# buck_schematic.net
KiCad netlist of a schematic drawn in EAGLE
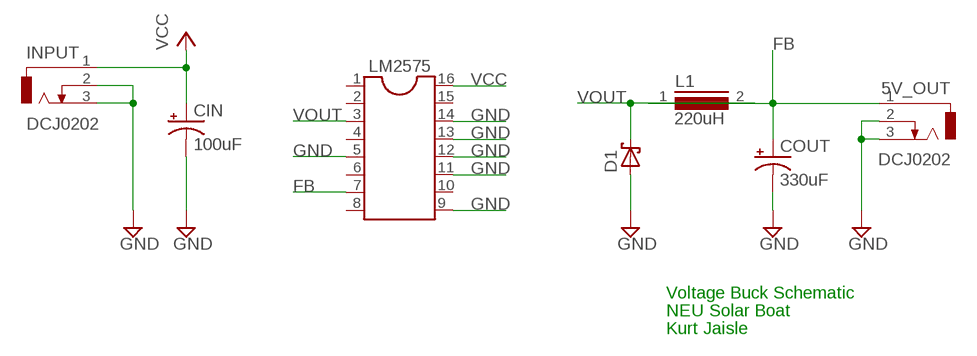
[diagram p0: schematic, sheet 1]

(export (version "E")
  (design (tool "Eeschema 10.0.6"))
  (components
    (comp (ref "5V_OUT")
      (value "DCJ0202")
      (footprint "eagle-import:DCJ0202")
      (libsource (lib "eagle-import") (part "DCJ0202"))
    )
    (comp (ref "CIN")
      (value "100uF")
      (footprint "eagle-import:E5-10,5")
      (libsource (lib "eagle-import") (part "CPOL-USE5-10.5"))
    )
    (comp (ref "COUT")
      (value "330uF")
      (footprint "eagle-import:E5-10,5")
      (libsource (lib "eagle-import") (part "CPOL-USE5-10.5"))
    )
    (comp (ref "D1")
      (value "SCHOTTKY-DIODEF126Z12")
      (footprint "eagle-import:F126Z12")
      (libsource (lib "eagle-import") (part "SCHOTTKY-DIODEF126Z12"))
    )
    (comp (ref "INPUT")
      (value "DCJ0202")
      (footprint "eagle-import:DCJ0202")
      (libsource (lib "eagle-import") (part "DCJ0202"))
    )
    (comp (ref "L1")
      (value "220uH")
      (footprint "eagle-import:SUKW3-27")
      (libsource (lib "eagle-import") (part "B82133"))
    )
    (comp (ref "LM2575")
      (value "DIL16")
      (footprint "eagle-import:DIL16")
      (libsource (lib "eagle-import") (part "DIL16"))
    )
  )
  (nets
    (net (code "1") (name "/FB") (class "Default")
      (node (ref "5V_OUT") (pin "1") (pinfunction "1_1") (pintype "passive"))
      (node (ref "COUT") (pin "+") (pinfunction "+_+") (pintype "passive"))
      (node (ref "L1") (pin "1") (pinfunction "1_1") (pintype "passive"))
      (node (ref "LM2575") (pin "7") (pinfunction "7_7") (pintype "passive"))
    )
    (net (code "2") (name "/VOUT") (class "Default")
      (node (ref "D1") (pin "C") (pinfunction "C_C") (pintype "passive"))
      (node (ref "L1") (pin "2") (pinfunction "2_2") (pintype "passive"))
      (node (ref "LM2575") (pin "3") (pinfunction "3_3") (pintype "passive"))
    )
    (net (code "3") (name "GND") (class "Default")
      (node (ref "5V_OUT") (pin "2") (pinfunction "2_2") (pintype "passive"))
      (node (ref "5V_OUT") (pin "3") (pinfunction "3_3") (pintype "passive"))
      (node (ref "CIN") (pin "-") (pinfunction "-_-") (pintype "passive"))
      (node (ref "COUT") (pin "-") (pinfunction "-_-") (pintype "passive"))
      (node (ref "D1") (pin "A") (pinfunction "A_A") (pintype "passive"))
      (node (ref "INPUT") (pin "2") (pinfunction "2_2") (pintype "passive"))
      (node (ref "INPUT") (pin "3") (pinfunction "3_3") (pintype "passive"))
      (node (ref "LM2575") (pin "11") (pinfunction "11_11") (pintype "passive"))
      (node (ref "LM2575") (pin "12") (pinfunction "12_12") (pintype "passive"))
      (node (ref "LM2575") (pin "13") (pinfunction "13_13") (pintype "passive"))
      (node (ref "LM2575") (pin "14") (pinfunction "14_14") (pintype "passive"))
      (node (ref "LM2575") (pin "5") (pinfunction "5_5") (pintype "passive"))
      (node (ref "LM2575") (pin "9") (pinfunction "9_9") (pintype "passive"))
    )
    (net (code "4") (name "VCC") (class "Default")
      (node (ref "CIN") (pin "+") (pinfunction "+_+") (pintype "passive"))
      (node (ref "INPUT") (pin "1") (pinfunction "1_1") (pintype "passive"))
      (node (ref "LM2575") (pin "16") (pinfunction "16_16") (pintype "passive"))
    )
    (net (code "5") (name "unconnected-(LM2575-Pad1)") (class "Default")
      (node (ref "LM2575") (pin "1") (pinfunction "1_1") (pintype "passive"))
    )
    (net (code "6") (name "unconnected-(LM2575-Pad2)") (class "Default")
      (node (ref "LM2575") (pin "2") (pinfunction "2_2") (pintype "passive"))
    )
    (net (code "7") (name "unconnected-(LM2575-Pad4)") (class "Default")
      (node (ref "LM2575") (pin "4") (pinfunction "4_4") (pintype "passive"))
    )
    (net (code "8") (name "unconnected-(LM2575-Pad6)") (class "Default")
      (node (ref "LM2575") (pin "6") (pinfunction "6_6") (pintype "passive"))
    )
    (net (code "9") (name "unconnected-(LM2575-Pad8)") (class "Default")
      (node (ref "LM2575") (pin "8") (pinfunction "8_8") (pintype "passive"))
    )
    (net (code "10") (name "unconnected-(LM2575-Pad10)") (class "Default")
      (node (ref "LM2575") (pin "10") (pinfunction "10_10") (pintype "passive"))
    )
    (net (code "11") (name "unconnected-(LM2575-Pad15)") (class "Default")
      (node (ref "LM2575") (pin "15") (pinfunction "15_15") (pintype "passive"))
    )
  )
)
